# K-Diag_small-_single-multi.net
KiCad netlist of a schematic drawn in EAGLE
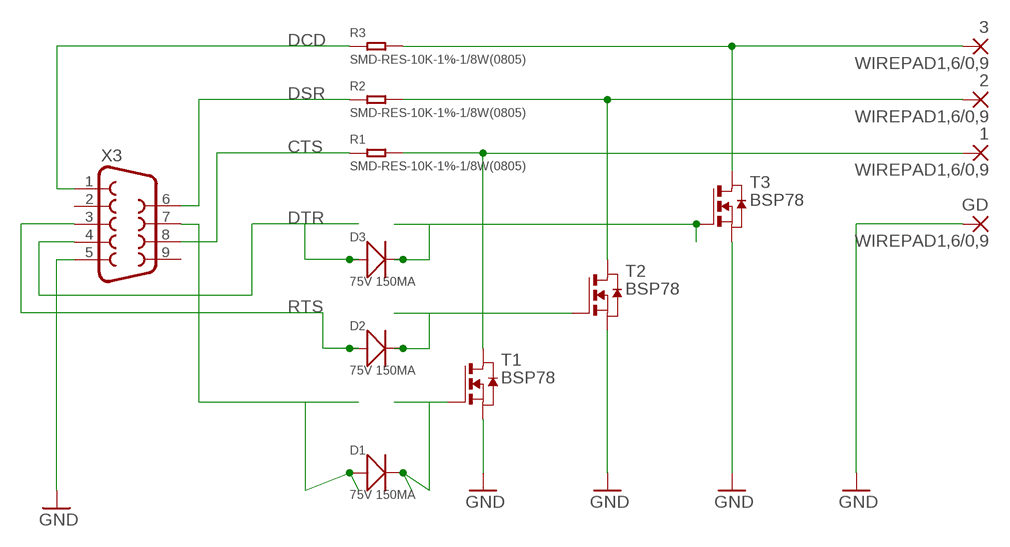
[diagram p0: schematic, sheet 1]
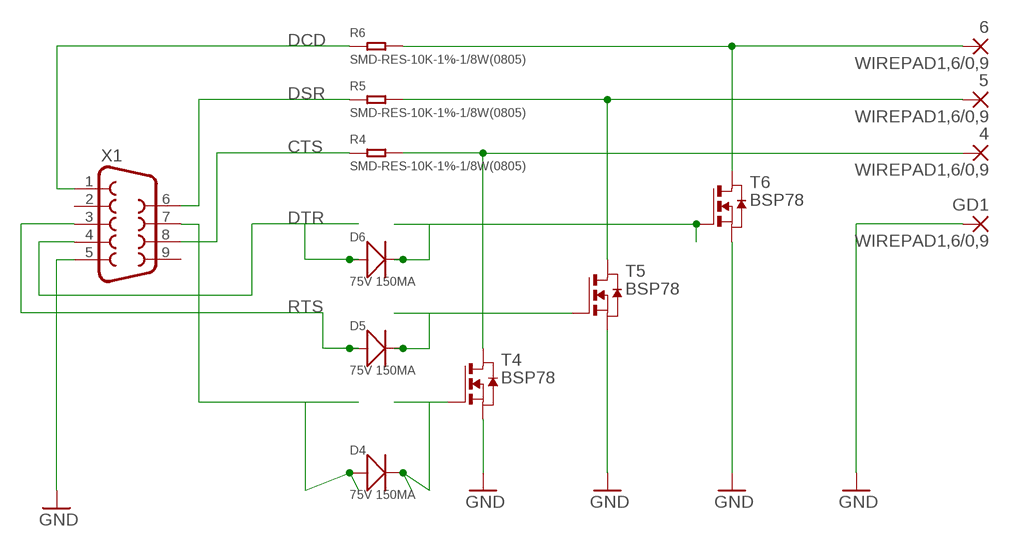
[diagram p1: schematic, sheet 2]
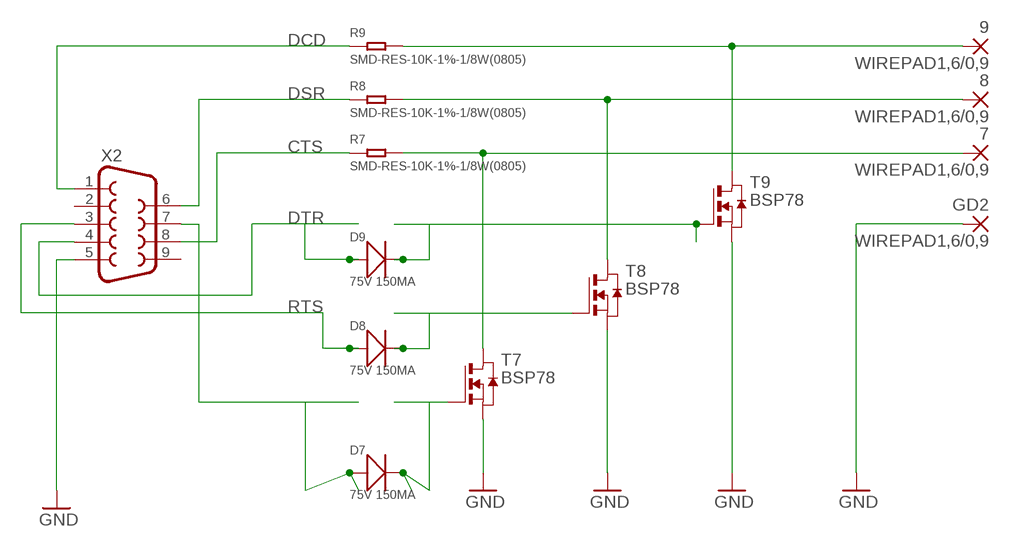
[diagram p2: schematic, sheet 3]
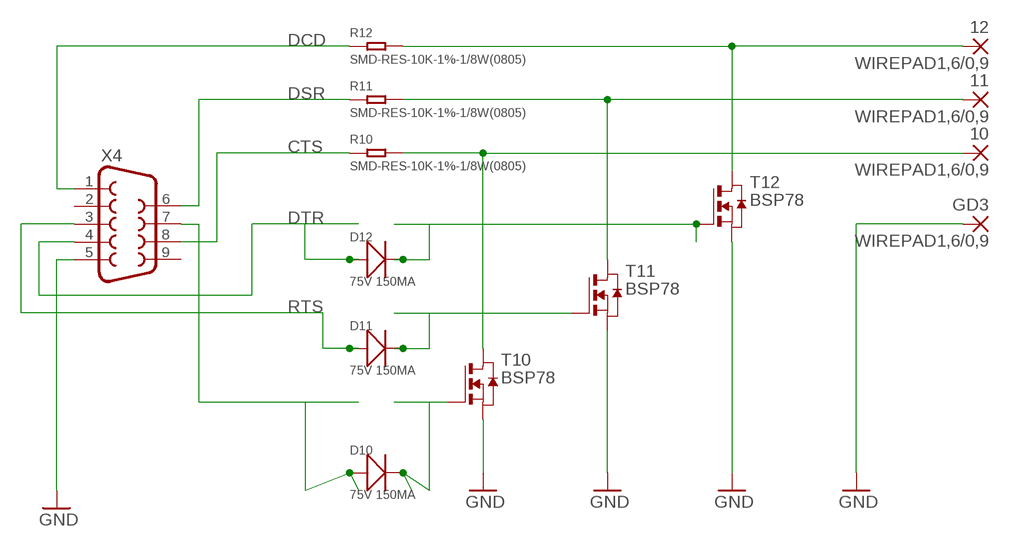
[diagram p3: schematic, sheet 4]

(export (version "E")
  (design (tool "Eeschema 10.0.6"))
  (components
    (comp (ref "4")
      (value "WIREPAD1,6/0,9")
      (footprint "eagle-import:1,6_0,9")
      (libsource (lib "eagle-import") (part "WIREPAD1,6/0,9"))
    )
    (comp (ref "5")
      (value "WIREPAD1,6/0,9")
      (footprint "eagle-import:1,6_0,9")
      (libsource (lib "eagle-import") (part "WIREPAD1,6/0,9"))
    )
    (comp (ref "6")
      (value "WIREPAD1,6/0,9")
      (footprint "eagle-import:1,6_0,9")
      (libsource (lib "eagle-import") (part "WIREPAD1,6/0,9"))
    )
    (comp (ref "D4")
      (value "75V 150MA")
      (footprint "eagle-import:LED-1206")
      (fields (field (name "MPN") "CD1206-S01575"))
      (libsource (lib "eagle-import") (part "SMD-DIODE-SWITCHING-75V-150MA(D1206)"))
    )
    (comp (ref "D5")
      (value "75V 150MA")
      (footprint "eagle-import:LED-1206")
      (fields (field (name "MPN") "CD1206-S01575"))
      (libsource (lib "eagle-import") (part "SMD-DIODE-SWITCHING-75V-150MA(D1206)"))
    )
    (comp (ref "D6")
      (value "75V 150MA")
      (footprint "eagle-import:LED-1206")
      (fields (field (name "MPN") "CD1206-S01575"))
      (libsource (lib "eagle-import") (part "SMD-DIODE-SWITCHING-75V-150MA(D1206)"))
    )
    (comp (ref "GD1")
      (value "WIREPAD1,6/0,9")
      (footprint "eagle-import:1,6_0,9")
      (libsource (lib "eagle-import") (part "WIREPAD1,6/0,9"))
    )
    (comp (ref "R4")
      (value "SMD-RES-10K-1%-1/8W(0805)")
      (footprint "eagle-import:R0805")
      (fields (field (name "MPN") "RC0805FR-0710KL"))
      (libsource (lib "eagle-import") (part "SMD-RES-10K-1%-1/8W(0805)"))
    )
    (comp (ref "R5")
      (value "SMD-RES-10K-1%-1/8W(0805)")
      (footprint "eagle-import:R0805")
      (fields (field (name "MPN") "RC0805FR-0710KL"))
      (libsource (lib "eagle-import") (part "SMD-RES-10K-1%-1/8W(0805)"))
    )
    (comp (ref "R6")
      (value "SMD-RES-10K-1%-1/8W(0805)")
      (footprint "eagle-import:R0805")
      (fields (field (name "MPN") "RC0805FR-0710KL"))
      (libsource (lib "eagle-import") (part "SMD-RES-10K-1%-1/8W(0805)"))
    )
    (comp (ref "T4")
      (value "BSP78")
      (footprint "eagle-import:SOT223")
      (libsource (lib "eagle-import") (part "NMOSSOT223"))
    )
    (comp (ref "T5")
      (value "BSP78")
      (footprint "eagle-import:SOT223")
      (libsource (lib "eagle-import") (part "NMOSSOT223"))
    )
    (comp (ref "T6")
      (value "BSP78")
      (footprint "eagle-import:SOT223")
      (libsource (lib "eagle-import") (part "NMOSSOT223"))
    )
    (comp (ref "X1")
      (value "F09D")
      (footprint "eagle-import:F09D")
      (libsource (lib "eagle-import") (part "F09D"))
    )
    (comp (ref "10")
      (value "WIREPAD1,6/0,9")
      (footprint "eagle-import:1,6_0,9")
      (libsource (lib "eagle-import") (part "WIREPAD1,6/0,9"))
    )
    (comp (ref "11")
      (value "WIREPAD1,6/0,9")
      (footprint "eagle-import:1,6_0,9")
      (libsource (lib "eagle-import") (part "WIREPAD1,6/0,9"))
    )
    (comp (ref "12")
      (value "WIREPAD1,6/0,9")
      (footprint "eagle-import:1,6_0,9")
      (libsource (lib "eagle-import") (part "WIREPAD1,6/0,9"))
    )
    (comp (ref "D10")
      (value "75V 150MA")
      (footprint "eagle-import:LED-1206")
      (fields (field (name "MPN") "CD1206-S01575"))
      (libsource (lib "eagle-import") (part "SMD-DIODE-SWITCHING-75V-150MA(D1206)"))
    )
    (comp (ref "D11")
      (value "75V 150MA")
      (footprint "eagle-import:LED-1206")
      (fields (field (name "MPN") "CD1206-S01575"))
      (libsource (lib "eagle-import") (part "SMD-DIODE-SWITCHING-75V-150MA(D1206)"))
    )
    (comp (ref "D12")
      (value "75V 150MA")
      (footprint "eagle-import:LED-1206")
      (fields (field (name "MPN") "CD1206-S01575"))
      (libsource (lib "eagle-import") (part "SMD-DIODE-SWITCHING-75V-150MA(D1206)"))
    )
    (comp (ref "GD3")
      (value "WIREPAD1,6/0,9")
      (footprint "eagle-import:1,6_0,9")
      (libsource (lib "eagle-import") (part "WIREPAD1,6/0,9"))
    )
    (comp (ref "R10")
      (value "SMD-RES-10K-1%-1/8W(0805)")
      (footprint "eagle-import:R0805")
      (fields (field (name "MPN") "RC0805FR-0710KL"))
      (libsource (lib "eagle-import") (part "SMD-RES-10K-1%-1/8W(0805)"))
    )
    (comp (ref "R11")
      (value "SMD-RES-10K-1%-1/8W(0805)")
      (footprint "eagle-import:R0805")
      (fields (field (name "MPN") "RC0805FR-0710KL"))
      (libsource (lib "eagle-import") (part "SMD-RES-10K-1%-1/8W(0805)"))
    )
    (comp (ref "R12")
      (value "SMD-RES-10K-1%-1/8W(0805)")
      (footprint "eagle-import:R0805")
      (fields (field (name "MPN") "RC0805FR-0710KL"))
      (libsource (lib "eagle-import") (part "SMD-RES-10K-1%-1/8W(0805)"))
    )
    (comp (ref "T10")
      (value "BSP78")
      (footprint "eagle-import:SOT223")
      (libsource (lib "eagle-import") (part "NMOSSOT223"))
    )
    (comp (ref "T11")
      (value "BSP78")
      (footprint "eagle-import:SOT223")
      (libsource (lib "eagle-import") (part "NMOSSOT223"))
    )
    (comp (ref "T12")
      (value "BSP78")
      (footprint "eagle-import:SOT223")
      (libsource (lib "eagle-import") (part "NMOSSOT223"))
    )
    (comp (ref "X4")
      (value "F09D")
      (footprint "eagle-import:F09D")
      (libsource (lib "eagle-import") (part "F09D"))
    )
    (comp (ref "1")
      (value "WIREPAD1,6/0,9")
      (footprint "eagle-import:1,6_0,9")
      (libsource (lib "eagle-import") (part "WIREPAD1,6/0,9"))
    )
    (comp (ref "2")
      (value "WIREPAD1,6/0,9")
      (footprint "eagle-import:1,6_0,9")
      (libsource (lib "eagle-import") (part "WIREPAD1,6/0,9"))
    )
    (comp (ref "3")
      (value "WIREPAD1,6/0,9")
      (footprint "eagle-import:1,6_0,9")
      (libsource (lib "eagle-import") (part "WIREPAD1,6/0,9"))
    )
    (comp (ref "D1")
      (value "75V 150MA")
      (footprint "eagle-import:LED-1206")
      (fields (field (name "MPN") "CD1206-S01575"))
      (libsource (lib "eagle-import") (part "SMD-DIODE-SWITCHING-75V-150MA(D1206)"))
    )
    (comp (ref "D2")
      (value "75V 150MA")
      (footprint "eagle-import:LED-1206")
      (fields (field (name "MPN") "CD1206-S01575"))
      (libsource (lib "eagle-import") (part "SMD-DIODE-SWITCHING-75V-150MA(D1206)"))
    )
    (comp (ref "D3")
      (value "75V 150MA")
      (footprint "eagle-import:LED-1206")
      (fields (field (name "MPN") "CD1206-S01575"))
      (libsource (lib "eagle-import") (part "SMD-DIODE-SWITCHING-75V-150MA(D1206)"))
    )
    (comp (ref "GD")
      (value "WIREPAD1,6/0,9")
      (footprint "eagle-import:1,6_0,9")
      (libsource (lib "eagle-import") (part "WIREPAD1,6/0,9"))
    )
    (comp (ref "R1")
      (value "SMD-RES-10K-1%-1/8W(0805)")
      (footprint "eagle-import:R0805")
      (fields (field (name "MPN") "RC0805FR-0710KL"))
      (libsource (lib "eagle-import") (part "SMD-RES-10K-1%-1/8W(0805)"))
    )
    (comp (ref "R2")
      (value "SMD-RES-10K-1%-1/8W(0805)")
      (footprint "eagle-import:R0805")
      (fields (field (name "MPN") "RC0805FR-0710KL"))
      (libsource (lib "eagle-import") (part "SMD-RES-10K-1%-1/8W(0805)"))
    )
    (comp (ref "R3")
      (value "SMD-RES-10K-1%-1/8W(0805)")
      (footprint "eagle-import:R0805")
      (fields (field (name "MPN") "RC0805FR-0710KL"))
      (libsource (lib "eagle-import") (part "SMD-RES-10K-1%-1/8W(0805)"))
    )
    (comp (ref "T1")
      (value "BSP78")
      (footprint "eagle-import:SOT223")
      (libsource (lib "eagle-import") (part "NMOSSOT223"))
    )
    (comp (ref "T2")
      (value "BSP78")
      (footprint "eagle-import:SOT223")
      (libsource (lib "eagle-import") (part "NMOSSOT223"))
    )
    (comp (ref "T3")
      (value "BSP78")
      (footprint "eagle-import:SOT223")
      (libsource (lib "eagle-import") (part "NMOSSOT223"))
    )
    (comp (ref "X3")
      (value "F09D")
      (footprint "eagle-import:F09D")
      (libsource (lib "eagle-import") (part "F09D"))
    )
    (comp (ref "7")
      (value "WIREPAD1,6/0,9")
      (footprint "eagle-import:1,6_0,9")
      (libsource (lib "eagle-import") (part "WIREPAD1,6/0,9"))
    )
    (comp (ref "8")
      (value "WIREPAD1,6/0,9")
      (footprint "eagle-import:1,6_0,9")
      (libsource (lib "eagle-import") (part "WIREPAD1,6/0,9"))
    )
    (comp (ref "9")
      (value "WIREPAD1,6/0,9")
      (footprint "eagle-import:1,6_0,9")
      (libsource (lib "eagle-import") (part "WIREPAD1,6/0,9"))
    )
    (comp (ref "D7")
      (value "75V 150MA")
      (footprint "eagle-import:LED-1206")
      (fields (field (name "MPN") "CD1206-S01575"))
      (libsource (lib "eagle-import") (part "SMD-DIODE-SWITCHING-75V-150MA(D1206)"))
    )
    (comp (ref "D8")
      (value "75V 150MA")
      (footprint "eagle-import:LED-1206")
      (fields (field (name "MPN") "CD1206-S01575"))
      (libsource (lib "eagle-import") (part "SMD-DIODE-SWITCHING-75V-150MA(D1206)"))
    )
    (comp (ref "D9")
      (value "75V 150MA")
      (footprint "eagle-import:LED-1206")
      (fields (field (name "MPN") "CD1206-S01575"))
      (libsource (lib "eagle-import") (part "SMD-DIODE-SWITCHING-75V-150MA(D1206)"))
    )
    (comp (ref "GD2")
      (value "WIREPAD1,6/0,9")
      (footprint "eagle-import:1,6_0,9")
      (libsource (lib "eagle-import") (part "WIREPAD1,6/0,9"))
    )
    (comp (ref "R7")
      (value "SMD-RES-10K-1%-1/8W(0805)")
      (footprint "eagle-import:R0805")
      (fields (field (name "MPN") "RC0805FR-0710KL"))
      (libsource (lib "eagle-import") (part "SMD-RES-10K-1%-1/8W(0805)"))
    )
    (comp (ref "R8")
      (value "SMD-RES-10K-1%-1/8W(0805)")
      (footprint "eagle-import:R0805")
      (fields (field (name "MPN") "RC0805FR-0710KL"))
      (libsource (lib "eagle-import") (part "SMD-RES-10K-1%-1/8W(0805)"))
    )
    (comp (ref "R9")
      (value "SMD-RES-10K-1%-1/8W(0805)")
      (footprint "eagle-import:R0805")
      (fields (field (name "MPN") "RC0805FR-0710KL"))
      (libsource (lib "eagle-import") (part "SMD-RES-10K-1%-1/8W(0805)"))
    )
    (comp (ref "T7")
      (value "BSP78")
      (footprint "eagle-import:SOT223")
      (libsource (lib "eagle-import") (part "NMOSSOT223"))
    )
    (comp (ref "T8")
      (value "BSP78")
      (footprint "eagle-import:SOT223")
      (libsource (lib "eagle-import") (part "NMOSSOT223"))
    )
    (comp (ref "T9")
      (value "BSP78")
      (footprint "eagle-import:SOT223")
      (libsource (lib "eagle-import") (part "NMOSSOT223"))
    )
    (comp (ref "X2")
      (value "F09D")
      (footprint "eagle-import:F09D")
      (libsource (lib "eagle-import") (part "F09D"))
    )
  )
  (nets
    (net (code "1") (name "CTS") (class "Default")
      (node (ref "R1") (pin "1") (pinfunction "1_1") (pintype "passive"))
      (node (ref "R10") (pin "1") (pinfunction "1_1") (pintype "passive"))
      (node (ref "R4") (pin "1") (pinfunction "1_1") (pintype "passive"))
      (node (ref "R7") (pin "1") (pinfunction "1_1") (pintype "passive"))
      (node (ref "X1") (pin "8") (pinfunction "8_8") (pintype "passive"))
      (node (ref "X2") (pin "8") (pinfunction "8_8") (pintype "passive"))
      (node (ref "X3") (pin "8") (pinfunction "8_8") (pintype "passive"))
      (node (ref "X4") (pin "8") (pinfunction "8_8") (pintype "passive"))
    )
    (net (code "2") (name "DCD") (class "Default")
      (node (ref "R12") (pin "1") (pinfunction "1_1") (pintype "passive"))
      (node (ref "R3") (pin "1") (pinfunction "1_1") (pintype "passive"))
      (node (ref "R6") (pin "1") (pinfunction "1_1") (pintype "passive"))
      (node (ref "R9") (pin "1") (pinfunction "1_1") (pintype "passive"))
      (node (ref "X1") (pin "1") (pinfunction "1_1") (pintype "passive"))
      (node (ref "X2") (pin "1") (pinfunction "1_1") (pintype "passive"))
      (node (ref "X3") (pin "1") (pinfunction "1_1") (pintype "passive"))
      (node (ref "X4") (pin "1") (pinfunction "1_1") (pintype "passive"))
    )
    (net (code "3") (name "DSR") (class "Default")
      (node (ref "R11") (pin "1") (pinfunction "1_1") (pintype "passive"))
      (node (ref "R2") (pin "1") (pinfunction "1_1") (pintype "passive"))
      (node (ref "R5") (pin "1") (pinfunction "1_1") (pintype "passive"))
      (node (ref "R8") (pin "1") (pinfunction "1_1") (pintype "passive"))
      (node (ref "X1") (pin "6") (pinfunction "6_6") (pintype "passive"))
      (node (ref "X2") (pin "6") (pinfunction "6_6") (pintype "passive"))
      (node (ref "X3") (pin "6") (pinfunction "6_6") (pintype "passive"))
      (node (ref "X4") (pin "6") (pinfunction "6_6") (pintype "passive"))
    )
    (net (code "4") (name "DTR") (class "Default")
      (node (ref "D12") (pin "+") (pinfunction "+_+") (pintype "passive"))
      (node (ref "D3") (pin "+") (pinfunction "+_+") (pintype "passive"))
      (node (ref "D6") (pin "+") (pinfunction "+_+") (pintype "passive"))
      (node (ref "D9") (pin "+") (pinfunction "+_+") (pintype "passive"))
      (node (ref "X1") (pin "4") (pinfunction "4_4") (pintype "passive"))
      (node (ref "X2") (pin "4") (pinfunction "4_4") (pintype "passive"))
      (node (ref "X3") (pin "4") (pinfunction "4_4") (pintype "passive"))
      (node (ref "X4") (pin "4") (pinfunction "4_4") (pintype "passive"))
    )
    (net (code "5") (name "GND") (class "Default")
      (node (ref "GD") (pin "1") (pinfunction "P_1") (pintype "passive"))
      (node (ref "GD1") (pin "1") (pinfunction "P_1") (pintype "passive"))
      (node (ref "GD2") (pin "1") (pinfunction "P_1") (pintype "passive"))
      (node (ref "GD3") (pin "1") (pinfunction "P_1") (pintype "passive"))
      (node (ref "T1") (pin "3") (pinfunction "S_3") (pintype "passive"))
      (node (ref "T10") (pin "3") (pinfunction "S_3") (pintype "passive"))
      (node (ref "T11") (pin "3") (pinfunction "S_3") (pintype "passive"))
      (node (ref "T12") (pin "3") (pinfunction "S_3") (pintype "passive"))
      (node (ref "T2") (pin "3") (pinfunction "S_3") (pintype "passive"))
      (node (ref "T3") (pin "3") (pinfunction "S_3") (pintype "passive"))
      (node (ref "T4") (pin "3") (pinfunction "S_3") (pintype "passive"))
      (node (ref "T5") (pin "3") (pinfunction "S_3") (pintype "passive"))
      (node (ref "T6") (pin "3") (pinfunction "S_3") (pintype "passive"))
      (node (ref "T7") (pin "3") (pinfunction "S_3") (pintype "passive"))
      (node (ref "T8") (pin "3") (pinfunction "S_3") (pintype "passive"))
      (node (ref "T9") (pin "3") (pinfunction "S_3") (pintype "passive"))
      (node (ref "X1") (pin "5") (pinfunction "5_5") (pintype "passive"))
      (node (ref "X2") (pin "5") (pinfunction "5_5") (pintype "passive"))
      (node (ref "X3") (pin "5") (pinfunction "5_5") (pintype "passive"))
      (node (ref "X4") (pin "5") (pinfunction "5_5") (pintype "passive"))
    )
    (net (code "6") (name "Net-(1-P)") (class "Default")
      (node (ref "1") (pin "1") (pinfunction "P_1") (pintype "passive"))
      (node (ref "R1") (pin "2") (pinfunction "2_2") (pintype "passive"))
      (node (ref "T1") (pin "2") (pinfunction "D_2") (pintype "passive"))
      (node (ref "T1") (pin "4") (pinfunction "D_4") (pintype "passive"))
    )
    (net (code "7") (name "Net-(2-P)") (class "Default")
      (node (ref "2") (pin "1") (pinfunction "P_1") (pintype "passive"))
      (node (ref "R2") (pin "2") (pinfunction "2_2") (pintype "passive"))
      (node (ref "T2") (pin "2") (pinfunction "D_2") (pintype "passive"))
      (node (ref "T2") (pin "4") (pinfunction "D_4") (pintype "passive"))
    )
    (net (code "8") (name "Net-(3-P)") (class "Default")
      (node (ref "3") (pin "1") (pinfunction "P_1") (pintype "passive"))
      (node (ref "R3") (pin "2") (pinfunction "2_2") (pintype "passive"))
      (node (ref "T3") (pin "2") (pinfunction "D_2") (pintype "passive"))
      (node (ref "T3") (pin "4") (pinfunction "D_4") (pintype "passive"))
    )
    (net (code "9") (name "Net-(4-P)") (class "Default")
      (node (ref "4") (pin "1") (pinfunction "P_1") (pintype "passive"))
      (node (ref "R4") (pin "2") (pinfunction "2_2") (pintype "passive"))
      (node (ref "T4") (pin "2") (pinfunction "D_2") (pintype "passive"))
      (node (ref "T4") (pin "4") (pinfunction "D_4") (pintype "passive"))
    )
    (net (code "10") (name "Net-(5-P)") (class "Default")
      (node (ref "5") (pin "1") (pinfunction "P_1") (pintype "passive"))
      (node (ref "R5") (pin "2") (pinfunction "2_2") (pintype "passive"))
      (node (ref "T5") (pin "2") (pinfunction "D_2") (pintype "passive"))
      (node (ref "T5") (pin "4") (pinfunction "D_4") (pintype "passive"))
    )
    (net (code "11") (name "Net-(6-P)") (class "Default")
      (node (ref "6") (pin "1") (pinfunction "P_1") (pintype "passive"))
      (node (ref "R6") (pin "2") (pinfunction "2_2") (pintype "passive"))
      (node (ref "T6") (pin "2") (pinfunction "D_2") (pintype "passive"))
      (node (ref "T6") (pin "4") (pinfunction "D_4") (pintype "passive"))
    )
    (net (code "12") (name "Net-(7-P)") (class "Default")
      (node (ref "7") (pin "1") (pinfunction "P_1") (pintype "passive"))
      (node (ref "R7") (pin "2") (pinfunction "2_2") (pintype "passive"))
      (node (ref "T7") (pin "2") (pinfunction "D_2") (pintype "passive"))
      (node (ref "T7") (pin "4") (pinfunction "D_4") (pintype "passive"))
    )
    (net (code "13") (name "Net-(8-P)") (class "Default")
      (node (ref "8") (pin "1") (pinfunction "P_1") (pintype "passive"))
      (node (ref "R8") (pin "2") (pinfunction "2_2") (pintype "passive"))
      (node (ref "T8") (pin "2") (pinfunction "D_2") (pintype "passive"))
      (node (ref "T8") (pin "4") (pinfunction "D_4") (pintype "passive"))
    )
    (net (code "14") (name "Net-(9-P)") (class "Default")
      (node (ref "9") (pin "1") (pinfunction "P_1") (pintype "passive"))
      (node (ref "R9") (pin "2") (pinfunction "2_2") (pintype "passive"))
      (node (ref "T9") (pin "2") (pinfunction "D_2") (pintype "passive"))
      (node (ref "T9") (pin "4") (pinfunction "D_4") (pintype "passive"))
    )
    (net (code "15") (name "Net-(10-P)") (class "Default")
      (node (ref "10") (pin "1") (pinfunction "P_1") (pintype "passive"))
      (node (ref "R10") (pin "2") (pinfunction "2_2") (pintype "passive"))
      (node (ref "T10") (pin "2") (pinfunction "D_2") (pintype "passive"))
      (node (ref "T10") (pin "4") (pinfunction "D_4") (pintype "passive"))
    )
    (net (code "16") (name "Net-(11-P)") (class "Default")
      (node (ref "11") (pin "1") (pinfunction "P_1") (pintype "passive"))
      (node (ref "R11") (pin "2") (pinfunction "2_2") (pintype "passive"))
      (node (ref "T11") (pin "2") (pinfunction "D_2") (pintype "passive"))
      (node (ref "T11") (pin "4") (pinfunction "D_4") (pintype "passive"))
    )
    (net (code "17") (name "Net-(12-P)") (class "Default")
      (node (ref "12") (pin "1") (pinfunction "P_1") (pintype "passive"))
      (node (ref "R12") (pin "2") (pinfunction "2_2") (pintype "passive"))
      (node (ref "T12") (pin "2") (pinfunction "D_2") (pintype "passive"))
      (node (ref "T12") (pin "4") (pinfunction "D_4") (pintype "passive"))
    )
    (net (code "18") (name "Net-(D1-Pad+)") (class "Default")
      (node (ref "D1") (pin "+") (pinfunction "+_+") (pintype "passive"))
      (node (ref "X3") (pin "7") (pinfunction "7_7") (pintype "passive"))
    )
    (net (code "19") (name "Net-(D4-Pad+)") (class "Default")
      (node (ref "D4") (pin "+") (pinfunction "+_+") (pintype "passive"))
      (node (ref "X1") (pin "7") (pinfunction "7_7") (pintype "passive"))
    )
    (net (code "20") (name "Net-(D7-Pad+)") (class "Default")
      (node (ref "D7") (pin "+") (pinfunction "+_+") (pintype "passive"))
      (node (ref "X2") (pin "7") (pinfunction "7_7") (pintype "passive"))
    )
    (net (code "21") (name "Net-(D10-Pad+)") (class "Default")
      (node (ref "D10") (pin "+") (pinfunction "+_+") (pintype "passive"))
      (node (ref "X4") (pin "7") (pinfunction "7_7") (pintype "passive"))
    )
    (net (code "22") (name "Net-(T1-G)") (class "Default")
      (node (ref "D1") (pin "-") (pinfunction "-_-") (pintype "passive"))
      (node (ref "T1") (pin "1") (pinfunction "G_1") (pintype "passive"))
    )
    (net (code "23") (name "Net-(T2-G)") (class "Default")
      (node (ref "D2") (pin "-") (pinfunction "-_-") (pintype "passive"))
      (node (ref "T2") (pin "1") (pinfunction "G_1") (pintype "passive"))
    )
    (net (code "24") (name "Net-(T3-G)") (class "Default")
      (node (ref "D3") (pin "-") (pinfunction "-_-") (pintype "passive"))
      (node (ref "T3") (pin "1") (pinfunction "G_1") (pintype "passive"))
    )
    (net (code "25") (name "Net-(T4-G)") (class "Default")
      (node (ref "D4") (pin "-") (pinfunction "-_-") (pintype "passive"))
      (node (ref "T4") (pin "1") (pinfunction "G_1") (pintype "passive"))
    )
    (net (code "26") (name "Net-(T5-G)") (class "Default")
      (node (ref "D5") (pin "-") (pinfunction "-_-") (pintype "passive"))
      (node (ref "T5") (pin "1") (pinfunction "G_1") (pintype "passive"))
    )
    (net (code "27") (name "Net-(T6-G)") (class "Default")
      (node (ref "D6") (pin "-") (pinfunction "-_-") (pintype "passive"))
      (node (ref "T6") (pin "1") (pinfunction "G_1") (pintype "passive"))
    )
    (net (code "28") (name "Net-(T7-G)") (class "Default")
      (node (ref "D7") (pin "-") (pinfunction "-_-") (pintype "passive"))
      (node (ref "T7") (pin "1") (pinfunction "G_1") (pintype "passive"))
    )
    (net (code "29") (name "Net-(T8-G)") (class "Default")
      (node (ref "D8") (pin "-") (pinfunction "-_-") (pintype "passive"))
      (node (ref "T8") (pin "1") (pinfunction "G_1") (pintype "passive"))
    )
    (net (code "30") (name "Net-(T9-G)") (class "Default")
      (node (ref "D9") (pin "-") (pinfunction "-_-") (pintype "passive"))
      (node (ref "T9") (pin "1") (pinfunction "G_1") (pintype "passive"))
    )
    (net (code "31") (name "Net-(T10-G)") (class "Default")
      (node (ref "D10") (pin "-") (pinfunction "-_-") (pintype "passive"))
      (node (ref "T10") (pin "1") (pinfunction "G_1") (pintype "passive"))
    )
    (net (code "32") (name "Net-(T11-G)") (class "Default")
      (node (ref "D11") (pin "-") (pinfunction "-_-") (pintype "passive"))
      (node (ref "T11") (pin "1") (pinfunction "G_1") (pintype "passive"))
    )
    (net (code "33") (name "Net-(T12-G)") (class "Default")
      (node (ref "D12") (pin "-") (pinfunction "-_-") (pintype "passive"))
      (node (ref "T12") (pin "1") (pinfunction "G_1") (pintype "passive"))
    )
    (net (code "34") (name "RTS") (class "Default")
      (node (ref "D11") (pin "+") (pinfunction "+_+") (pintype "passive"))
      (node (ref "D2") (pin "+") (pinfunction "+_+") (pintype "passive"))
      (node (ref "D5") (pin "+") (pinfunction "+_+") (pintype "passive"))
      (node (ref "D8") (pin "+") (pinfunction "+_+") (pintype "passive"))
      (node (ref "X1") (pin "3") (pinfunction "3_3") (pintype "passive"))
      (node (ref "X2") (pin "3") (pinfunction "3_3") (pintype "passive"))
      (node (ref "X3") (pin "3") (pinfunction "3_3") (pintype "passive"))
      (node (ref "X4") (pin "3") (pinfunction "3_3") (pintype "passive"))
    )
    (net (code "35") (name "unconnected-(X1-Pad2)") (class "Default")
      (node (ref "X1") (pin "2") (pinfunction "2_2") (pintype "passive"))
    )
    (net (code "36") (name "unconnected-(X1-Pad9)") (class "Default")
      (node (ref "X1") (pin "9") (pinfunction "9_9") (pintype "passive"))
    )
    (net (code "37") (name "unconnected-(X2-Pad2)") (class "Default")
      (node (ref "X2") (pin "2") (pinfunction "2_2") (pintype "passive"))
    )
    (net (code "38") (name "unconnected-(X2-Pad9)") (class "Default")
      (node (ref "X2") (pin "9") (pinfunction "9_9") (pintype "passive"))
    )
    (net (code "39") (name "unconnected-(X3-Pad2)") (class "Default")
      (node (ref "X3") (pin "2") (pinfunction "2_2") (pintype "passive"))
    )
    (net (code "40") (name "unconnected-(X3-Pad9)") (class "Default")
      (node (ref "X3") (pin "9") (pinfunction "9_9") (pintype "passive"))
    )
    (net (code "41") (name "unconnected-(X4-Pad2)") (class "Default")
      (node (ref "X4") (pin "2") (pinfunction "2_2") (pintype "passive"))
    )
    (net (code "42") (name "unconnected-(X4-Pad9)") (class "Default")
      (node (ref "X4") (pin "9") (pinfunction "9_9") (pintype "passive"))
    )
  )
)
